# 501_RPi0.net
KiCad netlist of a schematic drawn in Altium Designer
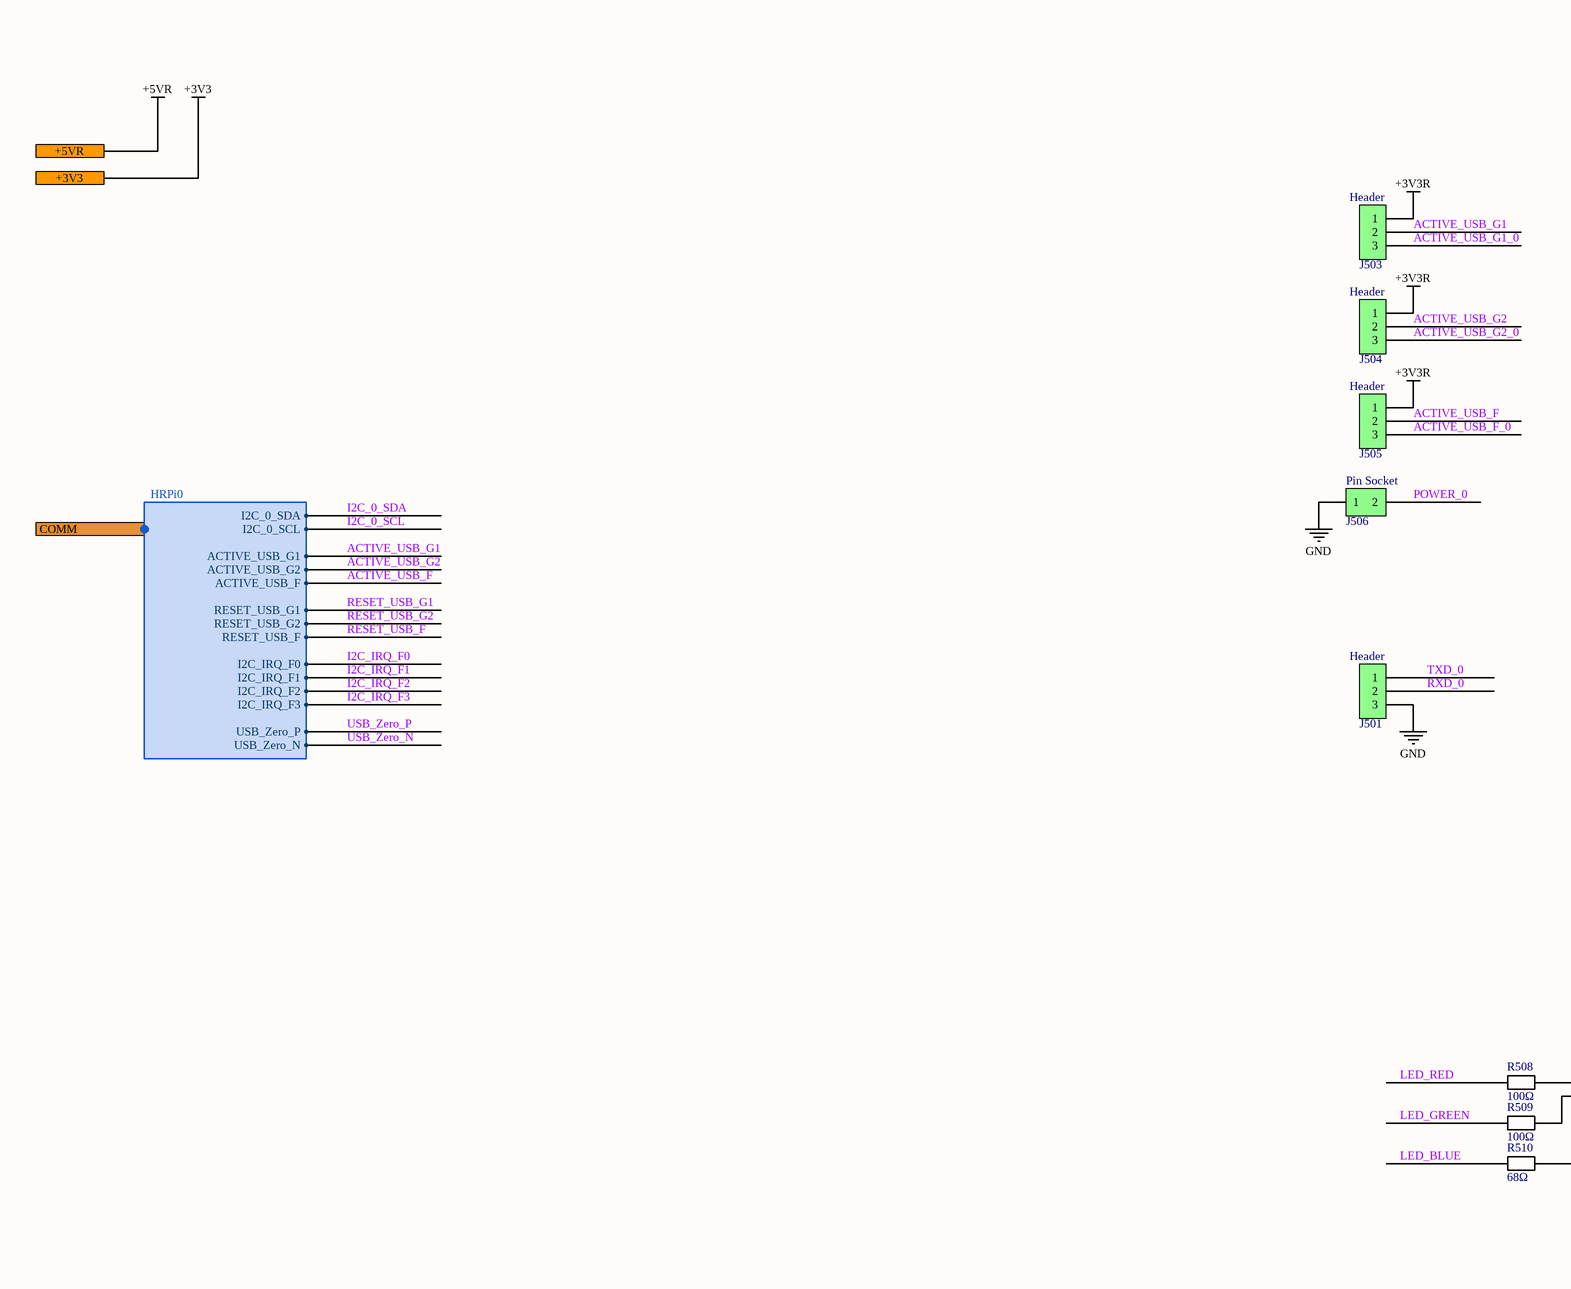
[diagram p0: 501_RPi0.SchDoc, left]
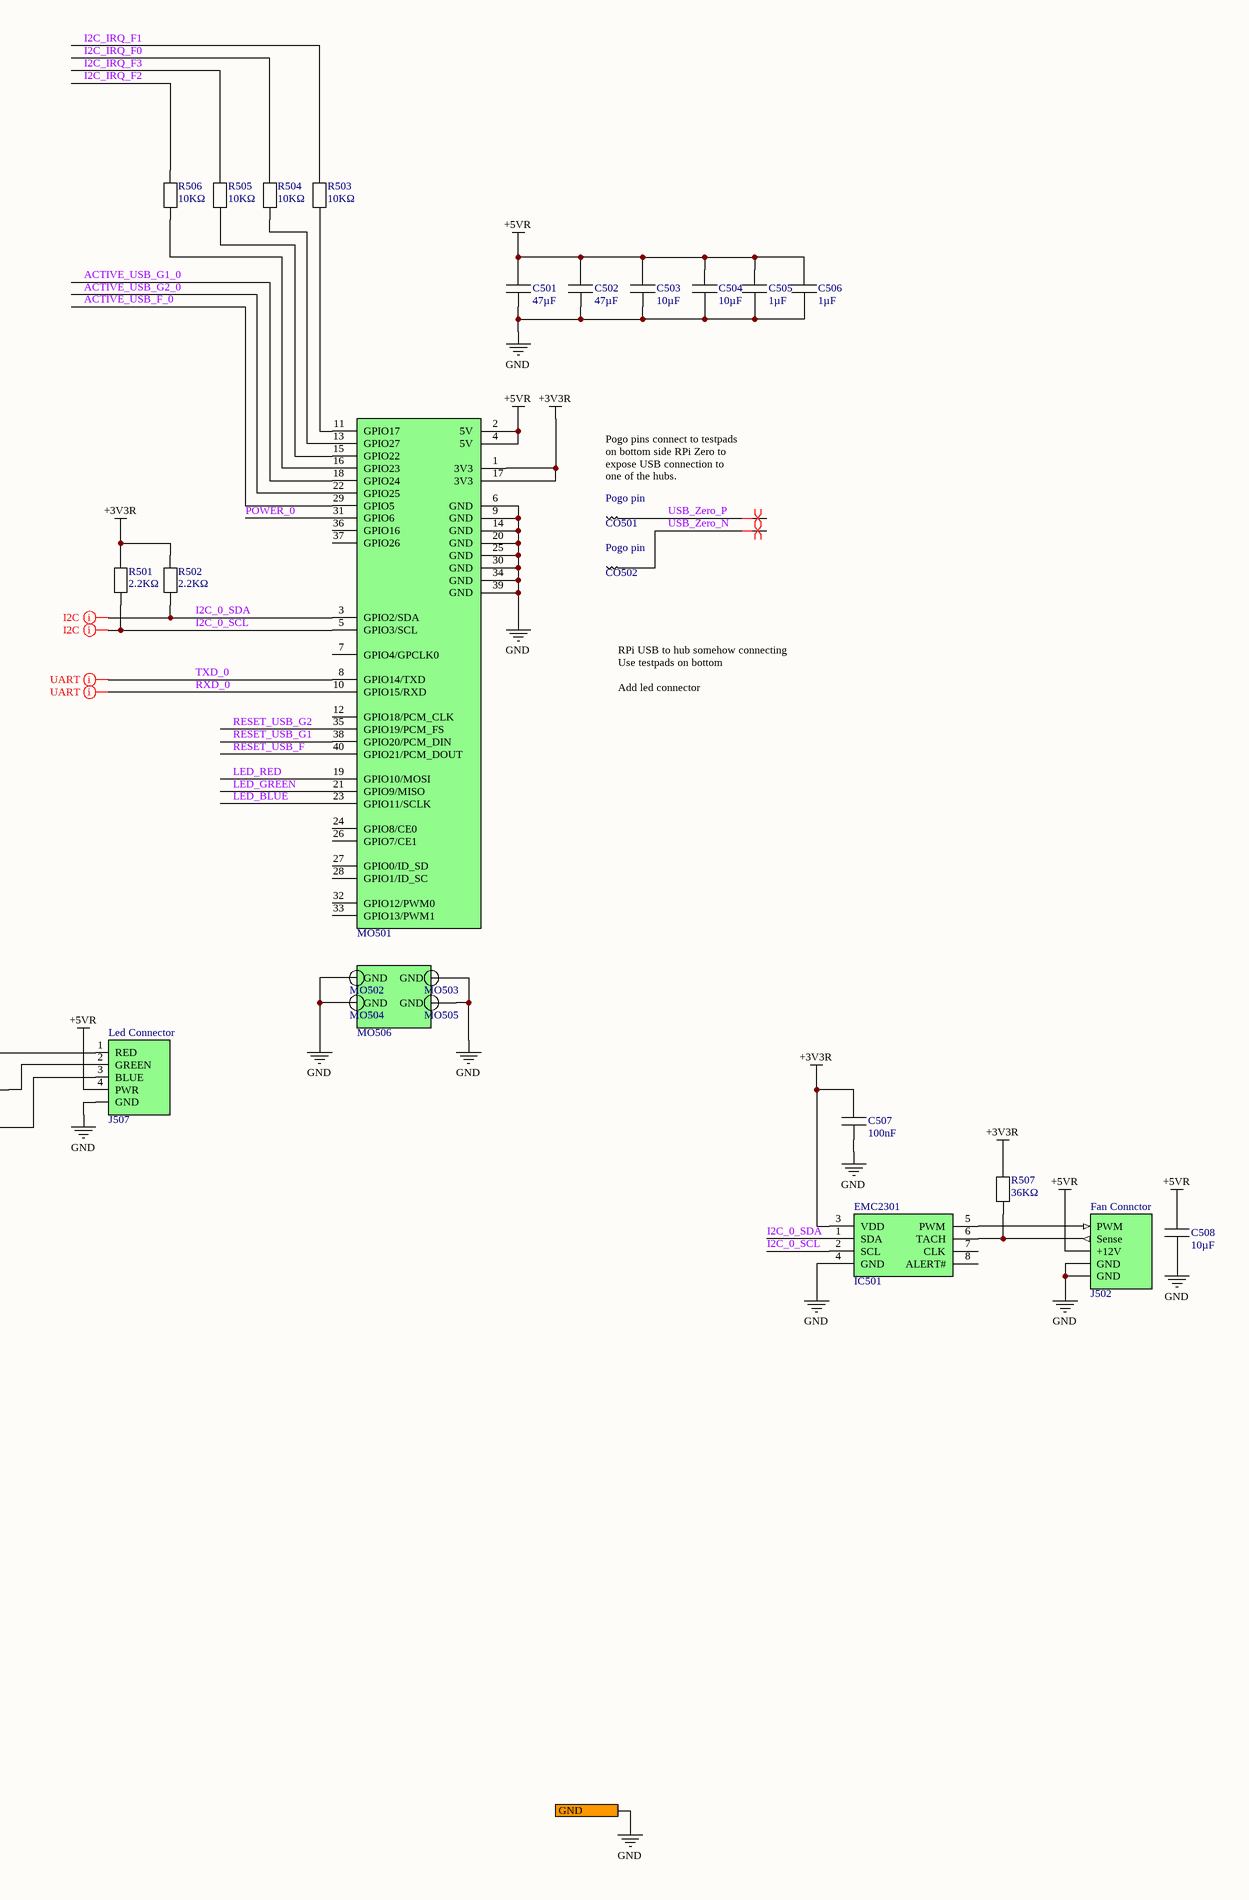
[diagram p1: 501_RPi0.SchDoc, right]

(export (version "E")
  (design (tool "Eeschema 10.0.6"))
  (components
    (comp (ref "C501")
      (value "47µF")
      (footprint "C1210")
      (description "47µF 16V 20% X5R")
      (fields
        (field (name "REFVAL") "47µF")
        (field (name "PART NUMBER") "CA0007")
        (field (name "MANFACTPART") "EMK325ABJ476MM8P")
      )
      (libsource (lib "GTS_Database") (part "C"))
    )
    (comp (ref "C502")
      (value "47µF")
      (footprint "C1210")
      (description "47µF 16V 20% X5R")
      (fields
        (field (name "REFVAL") "47µF")
        (field (name "PART NUMBER") "CA0007")
        (field (name "MANFACTPART") "EMK325ABJ476MM8P")
      )
      (libsource (lib "GTS_Database") (part "C"))
    )
    (comp (ref "C503")
      (value "10µF")
      (footprint "C0805")
      (description "10µF 16V 10% X5R")
      (fields
        (field (name "REFVAL") "10µF")
        (field (name "PART NUMBER") "CA0001")
        (field (name "MANFACTPART") "GRM21BR61C106KE15L")
      )
      (libsource (lib "GTS_Database") (part "C"))
    )
    (comp (ref "C504")
      (value "10µF")
      (footprint "C0805")
      (description "10µF 16V 10% X5R")
      (fields
        (field (name "REFVAL") "10µF")
        (field (name "PART NUMBER") "CA0001")
        (field (name "MANFACTPART") "GRM21BR61C106KE15L")
      )
      (libsource (lib "GTS_Database") (part "C"))
    )
    (comp (ref "C505")
      (value "1µF")
      (footprint "C0603")
      (description "1µF 16V 10% X5R")
      (fields
        (field (name "REFVAL") "1µF")
        (field (name "PART NUMBER") "CA0003")
        (field (name "MANFACTPART") "C1608X5R1C105K080AA")
      )
      (libsource (lib "GTS_Database") (part "C"))
    )
    (comp (ref "C506")
      (value "1µF")
      (footprint "C0603")
      (description "1µF 16V 10% X5R")
      (fields
        (field (name "REFVAL") "1µF")
        (field (name "PART NUMBER") "CA0003")
        (field (name "MANFACTPART") "C1608X5R1C105K080AA")
      )
      (libsource (lib "GTS_Database") (part "C"))
    )
    (comp (ref "C507")
      (value "100nF")
      (footprint "C0402")
      (description "100nF 16V 10% X7R")
      (fields
        (field (name "REFVAL") "100nF")
        (field (name "PART NUMBER") "CA0010")
        (field (name "MANFACTPART") "GCM155R71C104KA55D")
      )
      (libsource (lib "GTS_Database") (part "C"))
    )
    (comp (ref "C508")
      (value "10µF")
      (footprint "C0805")
      (description "10µF 16V 10% X5R")
      (fields
        (field (name "REFVAL") "10µF")
        (field (name "PART NUMBER") "CA0001")
        (field (name "MANFACTPART") "GRM21BR61C106KE15L")
      )
      (libsource (lib "GTS_Database") (part "C"))
    )
    (comp (ref "CO501")
      (value "Pogo pin")
      (footprint "POGO-0906")
      (description "Pogo pin 3mm TH")
      (fields
        (field (name "REFVAL") "Pogo pin")
        (field (name "PART NUMBER") "CO0058")
        (field (name "MANFACTPART") "0906-0-15-20-76-14-11-0")
      )
      (libsource (lib "GTS_Database") (part "POGO"))
    )
    (comp (ref "CO502")
      (value "Pogo pin")
      (footprint "POGO-0906")
      (description "Pogo pin 3mm TH")
      (fields
        (field (name "REFVAL") "Pogo pin")
        (field (name "PART NUMBER") "CO0058")
        (field (name "MANFACTPART") "0906-0-15-20-76-14-11-0")
      )
      (libsource (lib "GTS_Database") (part "POGO"))
    )
    (comp (ref "IC501")
      (value "EMC2301")
      (footprint "MSOP-8_3X3")
      (description "Board Mount Temperature Sensors Single RPB-Based PWM Fan Speed CNTRL")
      (fields
        (field (name "REFVAL") "EMC2301")
        (field (name "PART NUMBER") "IC0054")
        (field (name "MANFACTPART") "EMC2301-1-ACZL-TR")
      )
      (libsource (lib "GTS_Database") (part "EMC2301"))
    )
    (comp (ref "J501")
      (value "Header")
      (footprint "1X3P_2.54mm")
      (description "Header 1x3P")
      (fields
        (field (name "REFVAL") "Header")
        (field (name "PART NUMBER") "CO0018")
        (field (name "MANFACTPART") "G800W305018EU")
      )
      (libsource (lib "GTS_Database") (part "CONN1X3P"))
    )
    (comp (ref "J502")
      (value "Fan Connctor")
      (footprint "SM04B")
      (description "Connector Header SMD R/A 4POS 1MM")
      (fields
        (field (name "REFVAL") "Fan Connctor")
        (field (name "PART NUMBER") "CO0055")
        (field (name "MANFACTPART") "SM04B-SRSS-TB")
      )
      (libsource (lib "GTS_Database") (part "FAN4PG"))
    )
    (comp (ref "J503")
      (value "Header")
      (footprint "1X3P_2.54mm")
      (description "Header 1x3P")
      (fields
        (field (name "REFVAL") "Header")
        (field (name "PART NUMBER") "CO0018")
        (field (name "MANFACTPART") "G800W305018EU")
      )
      (libsource (lib "GTS_Database") (part "CONN1X3P"))
    )
    (comp (ref "J504")
      (value "Header")
      (footprint "1X3P_2.54mm")
      (description "Header 1x3P")
      (fields
        (field (name "REFVAL") "Header")
        (field (name "PART NUMBER") "CO0018")
        (field (name "MANFACTPART") "G800W305018EU")
      )
      (libsource (lib "GTS_Database") (part "CONN1X3P"))
    )
    (comp (ref "J505")
      (value "Header")
      (footprint "1X3P_2.54mm")
      (description "Header 1x3P")
      (fields
        (field (name "REFVAL") "Header")
        (field (name "PART NUMBER") "CO0018")
        (field (name "MANFACTPART") "G800W305018EU")
      )
      (libsource (lib "GTS_Database") (part "CONN1X3P"))
    )
    (comp (ref "J506")
      (value "Pin Socket")
      (footprint "1X2P_Socket_2.54mm")
      (description "Socket Strip with Square Tails")
      (fields
        (field (name "REFVAL") "Pin Socket")
        (field (name "PART NUMBER") "CO0060")
        (field (name "MANFACTPART") "SSQ-102-02-S-S")
      )
      (libsource (lib "GTS_Database") (part "CONN1X2P"))
    )
    (comp (ref "J507")
      (value "Led Connector")
      (footprint "SM04B")
      (description "Connector Header SMD R/A 4POS 1MM for LED4PG-15-23B/R6G6BHC-A01/2T")
      (fields
        (field (name "REFVAL") "Led Connector")
        (field (name "PART NUMBER") "CO0056")
        (field (name "MANFACTPART") "SM04B-SRSS-TB")
      )
      (libsource (lib "GTS_Database") (part "LED4PG-15-23B/R6G6BHC-A01/2T"))
    )
    (comp (ref "MO501")
      (value "ZeroW-1")
      (footprint "RPIZeroW_Pins")
      (description "RPI ZeroW Pin 1-40")
      (fields (field (name "PART NUMBER") "MO0018") (field (name "MANFACTPART") "61304021121"))
      (libsource (lib "GTS_Database") (part "RPIZeroW_Pins"))
    )
    (comp (ref "MO502")
      (value "ZeroW-M")
      (footprint "CM4-M")
      (description "RPI ZeroW Mounting Studs")
      (fields (field (name "PART NUMBER") "MO0016") (field (name "MANFACTPART") "9774030151R"))
      (libsource (lib "GTS_Database") (part "RPICM4_Mounting"))
    )
    (comp (ref "MO503")
      (value "ZeroW-M")
      (footprint "CM4-M")
      (description "RPI ZeroW Mounting Studs")
      (fields (field (name "PART NUMBER") "MO0016") (field (name "MANFACTPART") "9774030151R"))
      (libsource (lib "GTS_Database") (part "RPICM4_Mounting"))
    )
    (comp (ref "MO504")
      (value "ZeroW-M")
      (footprint "CM4-M")
      (description "RPI ZeroW Mounting Studs")
      (fields (field (name "PART NUMBER") "MO0016") (field (name "MANFACTPART") "9774030151R"))
      (libsource (lib "GTS_Database") (part "RPICM4_Mounting"))
    )
    (comp (ref "MO505")
      (value "ZeroW-M")
      (footprint "CM4-M")
      (description "RPI ZeroW Mounting Studs")
      (fields (field (name "PART NUMBER") "MO0016") (field (name "MANFACTPART") "9774030151R"))
      (libsource (lib "GTS_Database") (part "RPICM4_Mounting"))
    )
    (comp (ref "MO506")
      (value "ZeroW")
      (footprint "RPIZeroW_Layout")
      (description "Outline of ZeroW")
      (fields (field (name "PART NUMBER") "MO0015") (field (name "MANFACTPART") "RPI Zero W"))
      (libsource (lib "GTS_Database") (part "RPIZeroW_Layout"))
    )
    (comp (ref "R501")
      (value "2.2KΩ")
      (footprint "R0402")
      (description "2.2KΩ 5% 62.5mW")
      (fields
        (field (name "REFVAL") "2.2KΩ")
        (field (name "PART NUMBER") "RS0020")
        (field (name "MANFACTPART") "MCMR04X222 JTL")
      )
      (libsource (lib "GTS_Database") (part "R"))
    )
    (comp (ref "R502")
      (value "2.2KΩ")
      (footprint "R0402")
      (description "2.2KΩ 5% 62.5mW")
      (fields
        (field (name "REFVAL") "2.2KΩ")
        (field (name "PART NUMBER") "RS0020")
        (field (name "MANFACTPART") "MCMR04X222 JTL")
      )
      (libsource (lib "GTS_Database") (part "R"))
    )
    (comp (ref "R503")
      (value "10KΩ")
      (footprint "R0402")
      (description "10KΩ 1% 62.5mW")
      (fields
        (field (name "REFVAL") "10KΩ")
        (field (name "PART NUMBER") "RS0011")
        (field (name "MANFACTPART") "WR04X1002FTL")
      )
      (libsource (lib "GTS_Database") (part "R"))
    )
    (comp (ref "R504")
      (value "10KΩ")
      (footprint "R0402")
      (description "10KΩ 1% 62.5mW")
      (fields
        (field (name "REFVAL") "10KΩ")
        (field (name "PART NUMBER") "RS0011")
        (field (name "MANFACTPART") "WR04X1002FTL")
      )
      (libsource (lib "GTS_Database") (part "R"))
    )
    (comp (ref "R505")
      (value "10KΩ")
      (footprint "R0402")
      (description "10KΩ 1% 62.5mW")
      (fields
        (field (name "REFVAL") "10KΩ")
        (field (name "PART NUMBER") "RS0011")
        (field (name "MANFACTPART") "WR04X1002FTL")
      )
      (libsource (lib "GTS_Database") (part "R"))
    )
    (comp (ref "R506")
      (value "10KΩ")
      (footprint "R0402")
      (description "10KΩ 1% 62.5mW")
      (fields
        (field (name "REFVAL") "10KΩ")
        (field (name "PART NUMBER") "RS0011")
        (field (name "MANFACTPART") "WR04X1002FTL")
      )
      (libsource (lib "GTS_Database") (part "R"))
    )
    (comp (ref "R507")
      (value "36KΩ")
      (footprint "R0402")
      (description "36KΩ 1% 62.5mW 100PPM")
      (fields
        (field (name "REFVAL") "36KΩ")
        (field (name "PART NUMBER") "RS0051")
        (field (name "MANFACTPART") "ERJ-2RKF3602X")
      )
      (libsource (lib "GTS_Database") (part "R"))
    )
    (comp (ref "R508")
      (value "100Ω")
      (footprint "R0402")
      (description "120Ω 1% 62.5mW 100PPM")
      (fields
        (field (name "REFVAL") "100Ω")
        (field (name "PART NUMBER") "RS0082")
        (field (name "MANFACTPART") "CRG0402F120R")
      )
      (libsource (lib "GTS_Database") (part "R"))
    )
    (comp (ref "R509")
      (value "100Ω")
      (footprint "R0402")
      (description "120Ω 1% 62.5mW 100PPM")
      (fields
        (field (name "REFVAL") "100Ω")
        (field (name "PART NUMBER") "RS0082")
        (field (name "MANFACTPART") "CRG0402F120R")
      )
      (libsource (lib "GTS_Database") (part "R"))
    )
    (comp (ref "R510")
      (value "68Ω")
      (footprint "R0402")
      (description "68Ω 1% 62.5mW 100PPM")
      (fields
        (field (name "REFVAL") "68Ω")
        (field (name "PART NUMBER") "RS0081")
        (field (name "MANFACTPART") "CR0402-FX-68R0GLF")
      )
      (libsource (lib "GTS_Database") (part "R"))
    )
  )
  (nets
    (net (code "3") (name "+3V3R") (class "Default")
      (node (ref "C507") (pin "1") (pinfunction "1_1") (pintype "passive"))
      (node (ref "IC501") (pin "3") (pinfunction "VDD_3") (pintype "passive"))
      (node (ref "J503") (pin "1") (pinfunction "1_1") (pintype "passive"))
      (node (ref "J504") (pin "1") (pinfunction "1_1") (pintype "passive"))
      (node (ref "J505") (pin "1") (pinfunction "1_1") (pintype "passive"))
      (node (ref "MO501") (pin "1") (pinfunction "3V3_1") (pintype "passive"))
      (node (ref "MO501") (pin "17") (pinfunction "3V3_17") (pintype "passive"))
      (node (ref "R501") (pin "2") (pinfunction "2_2") (pintype "passive"))
      (node (ref "R502") (pin "2") (pinfunction "2_2") (pintype "passive"))
      (node (ref "R507") (pin "2") (pinfunction "2_2") (pintype "passive"))
    )
    (net (code "4") (name "+5VR") (class "Default")
      (node (ref "C501") (pin "1") (pinfunction "1_1") (pintype "passive"))
      (node (ref "C502") (pin "1") (pinfunction "1_1") (pintype "passive"))
      (node (ref "C503") (pin "1") (pinfunction "1_1") (pintype "passive"))
      (node (ref "C504") (pin "1") (pinfunction "1_1") (pintype "passive"))
      (node (ref "C505") (pin "1") (pinfunction "1_1") (pintype "passive"))
      (node (ref "C506") (pin "1") (pinfunction "1_1") (pintype "passive"))
      (node (ref "C508") (pin "1") (pinfunction "1_1") (pintype "passive"))
      (node (ref "J502") (pin "3") (pinfunction "+12V_3") (pintype "power_in"))
      (node (ref "J507") (pin "4") (pinfunction "PWR_4") (pintype "power_in"))
      (node (ref "MO501") (pin "2") (pinfunction "5V_2") (pintype "passive"))
      (node (ref "MO501") (pin "4") (pinfunction "5V_4") (pintype "passive"))
    )
    (net (code "5") (name "/ACTIVE_USB_F") (class "Default")
      (node (ref "J505") (pin "2") (pinfunction "2_2") (pintype "passive"))
    )
    (net (code "6") (name "/ACTIVE_USB_F_0") (class "Default")
      (node (ref "J505") (pin "3") (pinfunction "3_3") (pintype "passive"))
      (node (ref "MO501") (pin "29") (pinfunction "GPIO5_29") (pintype "passive"))
    )
    (net (code "7") (name "/ACTIVE_USB_G1") (class "Default")
      (node (ref "J503") (pin "2") (pinfunction "2_2") (pintype "passive"))
    )
    (net (code "8") (name "/ACTIVE_USB_G1_0") (class "Default")
      (node (ref "J503") (pin "3") (pinfunction "3_3") (pintype "passive"))
      (node (ref "MO501") (pin "18") (pinfunction "GPIO24_18") (pintype "passive"))
    )
    (net (code "9") (name "/ACTIVE_USB_G2") (class "Default")
      (node (ref "J504") (pin "2") (pinfunction "2_2") (pintype "passive"))
    )
    (net (code "10") (name "/ACTIVE_USB_G2_0") (class "Default")
      (node (ref "J504") (pin "3") (pinfunction "3_3") (pintype "passive"))
      (node (ref "MO501") (pin "22") (pinfunction "GPIO25_22") (pintype "passive"))
    )
    (net (code "11") (name "/I2C_0_SCL") (class "Default")
      (node (ref "IC501") (pin "2") (pinfunction "SCL_2") (pintype "passive"))
      (node (ref "MO501") (pin "5") (pinfunction "GPIO3/SCL_5") (pintype "passive"))
      (node (ref "R501") (pin "1") (pinfunction "1_1") (pintype "passive"))
    )
    (net (code "12") (name "/I2C_0_SDA") (class "Default")
      (node (ref "IC501") (pin "1") (pinfunction "SDA_1") (pintype "passive"))
      (node (ref "MO501") (pin "3") (pinfunction "GPIO2/SDA_3") (pintype "passive"))
      (node (ref "R502") (pin "1") (pinfunction "1_1") (pintype "passive"))
    )
    (net (code "13") (name "/I2C_IRQ_F0") (class "Default")
      (node (ref "R504") (pin "2") (pinfunction "2_2") (pintype "passive"))
    )
    (net (code "14") (name "/I2C_IRQ_F1") (class "Default")
      (node (ref "R503") (pin "2") (pinfunction "2_2") (pintype "passive"))
    )
    (net (code "15") (name "/I2C_IRQ_F2") (class "Default")
      (node (ref "R506") (pin "2") (pinfunction "2_2") (pintype "passive"))
    )
    (net (code "16") (name "/I2C_IRQ_F3") (class "Default")
      (node (ref "R505") (pin "2") (pinfunction "2_2") (pintype "passive"))
    )
    (net (code "17") (name "/LED_BLUE") (class "Default")
      (node (ref "MO501") (pin "23") (pinfunction "GPIO11/SCLK_23") (pintype "passive"))
      (node (ref "R510") (pin "1") (pinfunction "1_1") (pintype "passive"))
    )
    (net (code "18") (name "/LED_GREEN") (class "Default")
      (node (ref "MO501") (pin "21") (pinfunction "GPIO9/MISO_21") (pintype "passive"))
      (node (ref "R509") (pin "1") (pinfunction "1_1") (pintype "passive"))
    )
    (net (code "19") (name "/LED_RED") (class "Default")
      (node (ref "MO501") (pin "19") (pinfunction "GPIO10/MOSI_19") (pintype "passive"))
      (node (ref "R508") (pin "1") (pinfunction "1_1") (pintype "passive"))
    )
    (net (code "20") (name "/POWER_0") (class "Default")
      (node (ref "J506") (pin "2") (pinfunction "2_2") (pintype "passive"))
      (node (ref "MO501") (pin "31") (pinfunction "GPIO6_31") (pintype "passive"))
    )
    (net (code "21") (name "/RESET_USB_F") (class "Default")
      (node (ref "MO501") (pin "40") (pinfunction "GPIO21/PCM_DOUT_40") (pintype "passive"))
    )
    (net (code "22") (name "/RESET_USB_G1") (class "Default")
      (node (ref "MO501") (pin "38") (pinfunction "GPIO20/PCM_DIN_38") (pintype "passive"))
    )
    (net (code "23") (name "/RESET_USB_G2") (class "Default")
      (node (ref "MO501") (pin "35") (pinfunction "GPIO19/PCM_FS_35") (pintype "passive"))
    )
    (net (code "24") (name "/RXD_0") (class "Default")
      (node (ref "J501") (pin "2") (pinfunction "2_2") (pintype "passive"))
      (node (ref "MO501") (pin "10") (pinfunction "GPIO15/RXD_10") (pintype "passive"))
    )
    (net (code "25") (name "/TXD_0") (class "Default")
      (node (ref "J501") (pin "1") (pinfunction "1_1") (pintype "passive"))
      (node (ref "MO501") (pin "8") (pinfunction "GPIO14/TXD_8") (pintype "passive"))
    )
    (net (code "26") (name "/USB_Zero_N") (class "Default")
      (node (ref "CO502") (pin "1") (pinfunction "1_1") (pintype "passive"))
    )
    (net (code "27") (name "/USB_Zero_P") (class "Default")
      (node (ref "CO501") (pin "1") (pinfunction "1_1") (pintype "passive"))
    )
    (net (code "29") (name "GND") (class "Default")
      (node (ref "C501") (pin "2") (pinfunction "2_2") (pintype "passive"))
      (node (ref "C502") (pin "2") (pinfunction "2_2") (pintype "passive"))
      (node (ref "C503") (pin "2") (pinfunction "2_2") (pintype "passive"))
      (node (ref "C504") (pin "2") (pinfunction "2_2") (pintype "passive"))
      (node (ref "C505") (pin "2") (pinfunction "2_2") (pintype "passive"))
      (node (ref "C506") (pin "2") (pinfunction "2_2") (pintype "passive"))
      (node (ref "C507") (pin "2") (pinfunction "2_2") (pintype "passive"))
      (node (ref "C508") (pin "2") (pinfunction "2_2") (pintype "passive"))
      (node (ref "IC501") (pin "4") (pinfunction "GND_4") (pintype "passive"))
      (node (ref "J501") (pin "3") (pinfunction "3_3") (pintype "passive"))
      (node (ref "J502") (pin "4") (pinfunction "GND_4") (pintype "power_in"))
      (node (ref "J502") (pin "5") (pinfunction "GND_5") (pintype "power_in"))
      (node (ref "J506") (pin "1") (pinfunction "1_1") (pintype "passive"))
      (node (ref "J507") (pin "5") (pinfunction "GND_5") (pintype "power_in"))
      (node (ref "MO501") (pin "14") (pinfunction "GND_14") (pintype "passive"))
      (node (ref "MO501") (pin "20") (pinfunction "GND_20") (pintype "passive"))
      (node (ref "MO501") (pin "25") (pinfunction "GND_25") (pintype "passive"))
      (node (ref "MO501") (pin "30") (pinfunction "GND_30") (pintype "passive"))
      (node (ref "MO501") (pin "34") (pinfunction "GND_34") (pintype "passive"))
      (node (ref "MO501") (pin "39") (pinfunction "GND_39") (pintype "passive"))
      (node (ref "MO501") (pin "6") (pinfunction "GND_6") (pintype "passive"))
      (node (ref "MO501") (pin "9") (pinfunction "GND_9") (pintype "passive"))
      (node (ref "MO502") (pin "GND") (pinfunction "GND_GND") (pintype "passive"))
      (node (ref "MO503") (pin "GND") (pinfunction "GND_GND") (pintype "passive"))
      (node (ref "MO504") (pin "GND") (pinfunction "GND_GND") (pintype "passive"))
      (node (ref "MO505") (pin "GND") (pinfunction "GND_GND") (pintype "passive"))
    )
    (net (code "30") (name "Net-(IC501-PWM)") (class "Default")
      (node (ref "IC501") (pin "5") (pinfunction "PWM_5") (pintype "passive"))
      (node (ref "J502") (pin "1") (pinfunction "PWM_1") (pintype "input"))
    )
    (net (code "31") (name "Net-(IC501-TACH)") (class "Default")
      (node (ref "IC501") (pin "6") (pinfunction "TACH_6") (pintype "passive"))
      (node (ref "J502") (pin "2") (pinfunction "Sense_2") (pintype "output"))
      (node (ref "R507") (pin "1") (pinfunction "1_1") (pintype "passive"))
    )
    (net (code "32") (name "Net-(J507-BLUE)") (class "Default")
      (node (ref "J507") (pin "3") (pinfunction "BLUE_3") (pintype "power_in"))
      (node (ref "R510") (pin "2") (pinfunction "2_2") (pintype "passive"))
    )
    (net (code "33") (name "Net-(J507-GREEN)") (class "Default")
      (node (ref "J507") (pin "2") (pinfunction "GREEN_2") (pintype "passive"))
      (node (ref "R509") (pin "2") (pinfunction "2_2") (pintype "passive"))
    )
    (net (code "34") (name "Net-(J507-RED)") (class "Default")
      (node (ref "J507") (pin "1") (pinfunction "RED_1") (pintype "passive"))
      (node (ref "R508") (pin "2") (pinfunction "2_2") (pintype "passive"))
    )
    (net (code "35") (name "Net-(MO501-GPIO17)") (class "Default")
      (node (ref "MO501") (pin "11") (pinfunction "GPIO17_11") (pintype "passive"))
      (node (ref "R503") (pin "1") (pinfunction "1_1") (pintype "passive"))
    )
    (net (code "36") (name "Net-(MO501-GPIO22)") (class "Default")
      (node (ref "MO501") (pin "15") (pinfunction "GPIO22_15") (pintype "passive"))
      (node (ref "R505") (pin "1") (pinfunction "1_1") (pintype "passive"))
    )
    (net (code "37") (name "Net-(MO501-GPIO23)") (class "Default")
      (node (ref "MO501") (pin "16") (pinfunction "GPIO23_16") (pintype "passive"))
      (node (ref "R506") (pin "1") (pinfunction "1_1") (pintype "passive"))
    )
    (net (code "38") (name "Net-(MO501-GPIO27)") (class "Default")
      (node (ref "MO501") (pin "13") (pinfunction "GPIO27_13") (pintype "passive"))
      (node (ref "R504") (pin "1") (pinfunction "1_1") (pintype "passive"))
    )
    (net (code "39") (name "unconnected-(IC501-ALERT#-Pad8)") (class "Default")
      (node (ref "IC501") (pin "8") (pinfunction "ALERT#_8") (pintype "passive"))
    )
    (net (code "40") (name "unconnected-(IC501-CLK-Pad7)") (class "Default")
      (node (ref "IC501") (pin "7") (pinfunction "CLK_7") (pintype "passive"))
    )
    (net (code "41") (name "unconnected-(MO501-GPIO0{slash}ID_SD-Pad27)") (class "Default")
      (node (ref "MO501") (pin "27") (pinfunction "GPIO0/ID_SD_27") (pintype "passive"))
    )
    (net (code "42") (name "unconnected-(MO501-GPIO1{slash}ID_SC-Pad28)") (class "Default")
      (node (ref "MO501") (pin "28") (pinfunction "GPIO1/ID_SC_28") (pintype "passive"))
    )
    (net (code "43") (name "unconnected-(MO501-GPIO4{slash}GPCLK0-Pad7)") (class "Default")
      (node (ref "MO501") (pin "7") (pinfunction "GPIO4/GPCLK0_7") (pintype "passive"))
    )
    (net (code "44") (name "unconnected-(MO501-GPIO7{slash}CE1-Pad26)") (class "Default")
      (node (ref "MO501") (pin "26") (pinfunction "GPIO7/CE1_26") (pintype "passive"))
    )
    (net (code "45") (name "unconnected-(MO501-GPIO8{slash}CE0-Pad24)") (class "Default")
      (node (ref "MO501") (pin "24") (pinfunction "GPIO8/CE0_24") (pintype "passive"))
    )
    (net (code "46") (name "unconnected-(MO501-GPIO12{slash}PWM0-Pad32)") (class "Default")
      (node (ref "MO501") (pin "32") (pinfunction "GPIO12/PWM0_32") (pintype "passive"))
    )
    (net (code "47") (name "unconnected-(MO501-GPIO13{slash}PWM1-Pad33)") (class "Default")
      (node (ref "MO501") (pin "33") (pinfunction "GPIO13/PWM1_33") (pintype "passive"))
    )
    (net (code "48") (name "unconnected-(MO501-GPIO16-Pad36)") (class "Default")
      (node (ref "MO501") (pin "36") (pinfunction "GPIO16_36") (pintype "passive"))
    )
    (net (code "49") (name "unconnected-(MO501-GPIO18{slash}PCM_CLK-Pad12)") (class "Default")
      (node (ref "MO501") (pin "12") (pinfunction "GPIO18/PCM_CLK_12") (pintype "passive"))
    )
    (net (code "50") (name "unconnected-(MO501-GPIO26-Pad37)") (class "Default")
      (node (ref "MO501") (pin "37") (pinfunction "GPIO26_37") (pintype "passive"))
    )
  )
)
